# main_esp.net
KiCad netlist of a schematic drawn in Altium Designer
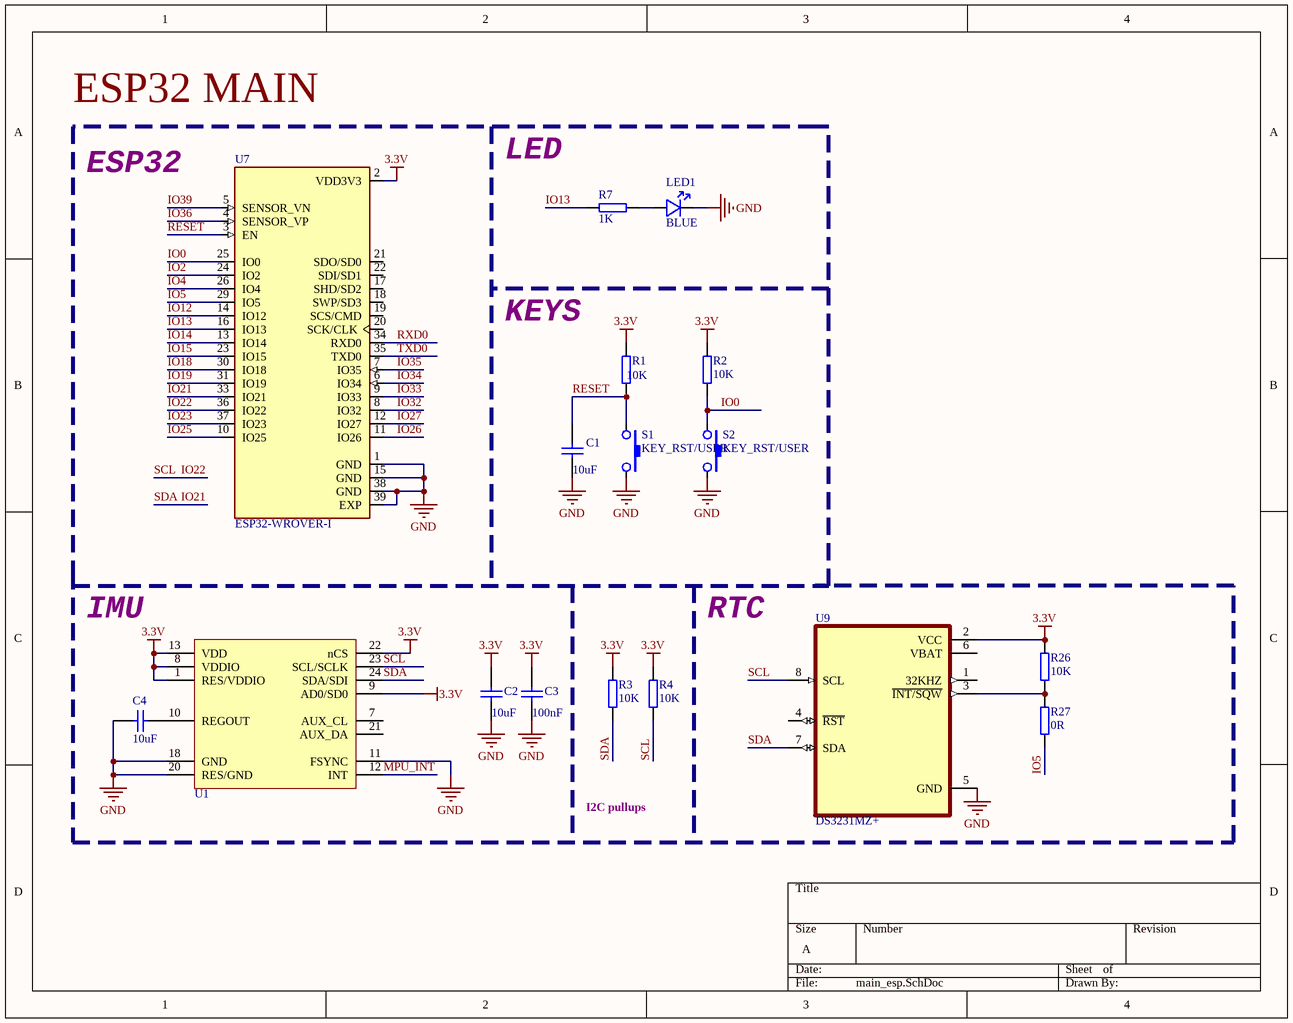
[diagram p0: main_esp.SchDoc]

(export (version "E")
  (design (tool "Eeschema 10.0.6"))
  (components
    (comp (ref "C1")
      (value "10uF")
      (footprint "SMT0603")
      (description "CAP SM 0603 X5R 10uF 10%")
      (fields (field (name "TOLERANCE") "±10%") (field (name "Comment") "Cap Semi"))
      (libsource (lib "electronpowered") (part "CAP-SM-0603-X5R-10uF"))
    )
    (comp (ref "C2")
      (value "10uF")
      (footprint "SMT0603")
      (description "CAP SM 0603 X5R 10uF 10%")
      (fields (field (name "TOLERANCE") "±10%") (field (name "Comment") "Cap Semi"))
      (libsource (lib "electronpowered") (part "CAP-SM-0603-X5R-10uF"))
    )
    (comp (ref "C3")
      (value "100nF")
      (footprint "SMT0603")
      (description "CAP SM 0603 X7R 100nF 10%")
      (fields (field (name "TOLERANCE") "±10%") (field (name "Comment") "Cap Semi"))
      (libsource (lib "electronpowered") (part "CAP-SM-0603-X7R-100nF"))
    )
    (comp (ref "C4")
      (value "10uF")
      (footprint "SMT0603")
      (description "CAP SM 0603 X5R 10uF 10%")
      (fields (field (name "TOLERANCE") "±10%") (field (name "Comment") "Cap Semi"))
      (libsource (lib "electronpowered") (part "CAP-SM-0603-X5R-10uF"))
    )
    (comp (ref "LED1")
      (value "BLUE")
      (footprint "SMT0603P")
      (description "LED SM 0603 BLUE 2V9 FWD VOLTAGE")
      (libsource (lib "electronpowered") (part "LNJ937W8CRA"))
    )
    (comp (ref "R1")
      (value "10K")
      (footprint "SMT0603")
      (description "RES SM 0603 10K")
      (fields (field (name "Comment") "Resistor"))
      (libsource (lib "electronpowered") (part "RES-SM-0603-10K"))
    )
    (comp (ref "R2")
      (value "10K")
      (footprint "SMT0603")
      (description "RES SM 0603 10K")
      (fields (field (name "Comment") "Resistor"))
      (libsource (lib "electronpowered") (part "RES-SM-0603-10K"))
    )
    (comp (ref "R3")
      (value "10K")
      (footprint "SMT0603")
      (description "RES SM 0603 10K")
      (fields (field (name "Comment") "Resistor"))
      (libsource (lib "electronpowered") (part "RES-SM-0603-10K"))
    )
    (comp (ref "R4")
      (value "10K")
      (footprint "SMT0603")
      (description "RES SM 0603 10K")
      (fields (field (name "Comment") "Resistor"))
      (libsource (lib "electronpowered") (part "RES-SM-0603-10K"))
    )
    (comp (ref "R7")
      (value "1K")
      (footprint "SMT0603")
      (description "RES SM 0603 1K")
      (fields (field (name "Comment") "Resistor"))
      (libsource (lib "electronpowered") (part "RES-SM-0603-1K"))
    )
    (comp (ref "R26")
      (value "10K")
      (footprint "SMT0603")
      (description "RES SM 0603 10K")
      (fields (field (name "Comment") "Resistor"))
      (libsource (lib "electronpowered") (part "RES-SM-0603-10K"))
    )
    (comp (ref "R27")
      (value "0R")
      (footprint "SMT0603")
      (description "RES SM 0603 10K")
      (fields (field (name "Comment") "Resistor"))
      (libsource (lib "electronpowered") (part "RES-SM-0603-10K"))
    )
    (comp (ref "S1")
      (value "KEY_RST/USER")
      (footprint "SMT_SW_PTS_820")
      (description "SMT Tactile ‎Switch PTS 820 Series")
      (libsource (lib "NODEMCU_DEVKIT_V1.0") (part "SMT_SW_PTS_820"))
    )
    (comp (ref "S2")
      (value "KEY_RST/USER")
      (footprint "SMT_SW_PTS_820")
      (description "SMT Tactile ‎Switch PTS 820 Series")
      (libsource (lib "NODEMCU_DEVKIT_V1.0") (part "SMT_SW_PTS_820"))
    )
    (comp (ref "U1") (value "MPU-9250") (libsource (lib "MPU-9250") (part "MPU-9250")))
    (comp (ref "U7")
      (value "ESP32-WROVER-I")
      (footprint "SnapEDApcb:XCVR_ESP32-WROVER-I")
      (fields (field (name "MF") "Espressif Systems"))
      (libsource (lib "SnapEDAsch") (part "ESP32-WROVER-I"))
    )
    (comp (ref "U9")
      (value "DS3231MZ+")
      (footprint "SOIC127P600X175-8N")
      (description "Real Time Clock _RTC_ IC Clock/Calendar IÂ²C, 2-Wire Serial 8-SOIC _0.154, 3.90mm Width_")
      (fields (field (name "MP") "DS3231MZ") (field (name "MF") "Maxim Integrated"))
      (libsource (lib "DS3231MZ_") (part "DS3231MZ+"))
    )
  )
  (nets
    (net (code "1") (name "/IO0") (class "Default")
      (node (ref "R2") (pin "1") (pinfunction "1_1") (pintype "passive"))
      (node (ref "S2") (pin "1") (pinfunction "1_1") (pintype "passive"))
      (node (ref "U7") (pin "25") (pinfunction "IO0_25") (pintype "bidirectional"))
    )
    (net (code "2") (name "/IO2") (class "Default")
      (node (ref "U7") (pin "24") (pinfunction "IO2_24") (pintype "bidirectional"))
    )
    (net (code "3") (name "/IO4") (class "Default")
      (node (ref "U7") (pin "26") (pinfunction "IO4_26") (pintype "bidirectional"))
    )
    (net (code "4") (name "/IO5") (class "Default")
      (node (ref "R27") (pin "2") (pinfunction "2_2") (pintype "passive"))
      (node (ref "U7") (pin "29") (pinfunction "IO5_29") (pintype "bidirectional"))
    )
    (net (code "5") (name "/IO12") (class "Default")
      (node (ref "U7") (pin "14") (pinfunction "IO12_14") (pintype "bidirectional"))
    )
    (net (code "6") (name "/IO13") (class "Default")
      (node (ref "R7") (pin "1") (pinfunction "1_1") (pintype "passive"))
      (node (ref "U7") (pin "16") (pinfunction "IO13_16") (pintype "bidirectional"))
    )
    (net (code "7") (name "/IO14") (class "Default")
      (node (ref "U7") (pin "13") (pinfunction "IO14_13") (pintype "bidirectional"))
    )
    (net (code "8") (name "/IO15") (class "Default")
      (node (ref "U7") (pin "23") (pinfunction "IO15_23") (pintype "bidirectional"))
    )
    (net (code "9") (name "/IO18") (class "Default")
      (node (ref "U7") (pin "30") (pinfunction "IO18_30") (pintype "bidirectional"))
    )
    (net (code "10") (name "/IO19") (class "Default")
      (node (ref "U7") (pin "31") (pinfunction "IO19_31") (pintype "bidirectional"))
    )
    (net (code "11") (name "/IO21") (class "Default")
      (node (ref "R3") (pin "1") (pinfunction "1_1") (pintype "passive"))
      (node (ref "U1") (pin "24") (pinfunction "SDA/SDI_24") (pintype "passive"))
      (node (ref "U7") (pin "33") (pinfunction "IO21_33") (pintype "bidirectional"))
      (node (ref "U9") (pin "7") (pinfunction "SDA_7") (pintype "bidirectional"))
    )
    (net (code "12") (name "/IO22") (class "Default")
      (node (ref "R4") (pin "1") (pinfunction "1_1") (pintype "passive"))
      (node (ref "U1") (pin "23") (pinfunction "SCL/SCLK_23") (pintype "passive"))
      (node (ref "U7") (pin "36") (pinfunction "IO22_36") (pintype "bidirectional"))
      (node (ref "U9") (pin "8") (pinfunction "SCL_8") (pintype "input"))
    )
    (net (code "13") (name "/IO23") (class "Default")
      (node (ref "U7") (pin "37") (pinfunction "IO23_37") (pintype "bidirectional"))
    )
    (net (code "14") (name "/IO25") (class "Default")
      (node (ref "U7") (pin "10") (pinfunction "IO25_10") (pintype "bidirectional"))
    )
    (net (code "15") (name "/IO26") (class "Default")
      (node (ref "U7") (pin "11") (pinfunction "IO26_11") (pintype "bidirectional"))
    )
    (net (code "16") (name "/IO27") (class "Default")
      (node (ref "U7") (pin "12") (pinfunction "IO27_12") (pintype "bidirectional"))
    )
    (net (code "17") (name "/IO32") (class "Default")
      (node (ref "U7") (pin "8") (pinfunction "IO32_8") (pintype "bidirectional"))
    )
    (net (code "18") (name "/IO33") (class "Default")
      (node (ref "U7") (pin "9") (pinfunction "IO33_9") (pintype "bidirectional"))
    )
    (net (code "19") (name "/IO34") (class "Default")
      (node (ref "U7") (pin "6") (pinfunction "IO34_6") (pintype "input"))
    )
    (net (code "20") (name "/IO35") (class "Default")
      (node (ref "U7") (pin "7") (pinfunction "IO35_7") (pintype "input"))
    )
    (net (code "21") (name "/IO36") (class "Default")
      (node (ref "U7") (pin "4") (pinfunction "SENSOR_VP_4") (pintype "input"))
    )
    (net (code "22") (name "/IO39") (class "Default")
      (node (ref "U7") (pin "5") (pinfunction "SENSOR_VN_5") (pintype "input"))
    )
    (net (code "23") (name "/MPU_INT") (class "Default")
      (node (ref "U1") (pin "12") (pinfunction "INT_12") (pintype "passive"))
    )
    (net (code "24") (name "/RESET") (class "Default")
      (node (ref "C1") (pin "2") (pinfunction "2_2") (pintype "passive"))
      (node (ref "R1") (pin "1") (pinfunction "1_1") (pintype "passive"))
      (node (ref "S1") (pin "1") (pinfunction "1_1") (pintype "passive"))
      (node (ref "U7") (pin "3") (pinfunction "EN_3") (pintype "input"))
    )
    (net (code "25") (name "/RXD0") (class "Default")
      (node (ref "U7") (pin "34") (pinfunction "RXD0_34") (pintype "bidirectional"))
    )
    (net (code "26") (name "/TXD0") (class "Default")
      (node (ref "U7") (pin "35") (pinfunction "TXD0_35") (pintype "bidirectional"))
    )
    (net (code "27") (name "3.3V") (class "Default")
      (node (ref "C2") (pin "2") (pinfunction "2_2") (pintype "passive"))
      (node (ref "C3") (pin "2") (pinfunction "2_2") (pintype "passive"))
      (node (ref "R1") (pin "2") (pinfunction "2_2") (pintype "passive"))
      (node (ref "R2") (pin "2") (pinfunction "2_2") (pintype "passive"))
      (node (ref "R26") (pin "1") (pinfunction "1_1") (pintype "passive"))
      (node (ref "R3") (pin "2") (pinfunction "2_2") (pintype "passive"))
      (node (ref "R4") (pin "2") (pinfunction "2_2") (pintype "passive"))
      (node (ref "U1") (pin "1") (pinfunction "RES/VDDIO_1") (pintype "passive"))
      (node (ref "U1") (pin "13") (pinfunction "VDD_13") (pintype "passive"))
      (node (ref "U1") (pin "22") (pinfunction "nCS_22") (pintype "passive"))
      (node (ref "U1") (pin "8") (pinfunction "VDDIO_8") (pintype "passive"))
      (node (ref "U1") (pin "9") (pinfunction "AD0/SD0_9") (pintype "passive"))
      (node (ref "U7") (pin "2") (pinfunction "VDD3V3_2") (pintype "power_in"))
      (node (ref "U9") (pin "2") (pinfunction "VCC_2") (pintype "power_in"))
    )
    (net (code "28") (name "GND") (class "Default")
      (node (ref "C1") (pin "1") (pinfunction "1_1") (pintype "passive"))
      (node (ref "C2") (pin "1") (pinfunction "1_1") (pintype "passive"))
      (node (ref "C3") (pin "1") (pinfunction "1_1") (pintype "passive"))
      (node (ref "C4") (pin "2") (pinfunction "2_2") (pintype "passive"))
      (node (ref "LED1") (pin "2") (pinfunction "2_2") (pintype "passive"))
      (node (ref "S1") (pin "2") (pinfunction "2_2") (pintype "passive"))
      (node (ref "S2") (pin "2") (pinfunction "2_2") (pintype "passive"))
      (node (ref "U1") (pin "11") (pinfunction "FSYNC_11") (pintype "passive"))
      (node (ref "U1") (pin "18") (pinfunction "GND_18") (pintype "passive"))
      (node (ref "U1") (pin "20") (pinfunction "RES/GND_20") (pintype "passive"))
      (node (ref "U7") (pin "1") (pinfunction "GND_1") (pintype "power_in"))
      (node (ref "U7") (pin "15") (pinfunction "GND_15") (pintype "power_in"))
      (node (ref "U7") (pin "38") (pinfunction "GND_38") (pintype "power_in"))
      (node (ref "U7") (pin "39") (pinfunction "EXP_39") (pintype "power_in"))
      (node (ref "U9") (pin "5") (pinfunction "GND_5") (pintype "power_in"))
    )
    (net (code "29") (name "Net-(LED1-Pad1)") (class "Default")
      (node (ref "LED1") (pin "1") (pinfunction "1_1") (pintype "passive"))
      (node (ref "R7") (pin "2") (pinfunction "2_2") (pintype "passive"))
    )
    (net (code "30") (name "Net-(U1-REGOUT)") (class "Default")
      (node (ref "C4") (pin "1") (pinfunction "1_1") (pintype "passive"))
      (node (ref "U1") (pin "10") (pinfunction "REGOUT_10") (pintype "passive"))
    )
    (net (code "31") (name "Net-(U9-~{INT{slash}SQW})") (class "Default")
      (node (ref "R26") (pin "2") (pinfunction "2_2") (pintype "passive"))
      (node (ref "R27") (pin "1") (pinfunction "1_1") (pintype "passive"))
      (node (ref "U9") (pin "3") (pinfunction "~{INT/SQW}_3") (pintype "output"))
    )
    (net (code "32") (name "unconnected-(U1-AUX_CL-Pad7)") (class "Default")
      (node (ref "U1") (pin "7") (pinfunction "AUX_CL_7") (pintype "passive"))
    )
    (net (code "33") (name "unconnected-(U1-AUX_DA-Pad21)") (class "Default")
      (node (ref "U1") (pin "21") (pinfunction "AUX_DA_21") (pintype "passive"))
    )
    (net (code "34") (name "unconnected-(U7-SCK{slash}CLK-Pad20)") (class "Default")
      (node (ref "U7") (pin "20") (pinfunction "SCK/CLK_20") (pintype "bidirectional"))
    )
    (net (code "35") (name "unconnected-(U7-SCS{slash}CMD-Pad19)") (class "Default")
      (node (ref "U7") (pin "19") (pinfunction "SCS/CMD_19") (pintype "bidirectional"))
    )
    (net (code "36") (name "unconnected-(U7-SDI{slash}SD1-Pad22)") (class "Default")
      (node (ref "U7") (pin "22") (pinfunction "SDI/SD1_22") (pintype "bidirectional"))
    )
    (net (code "37") (name "unconnected-(U7-SDO{slash}SD0-Pad21)") (class "Default")
      (node (ref "U7") (pin "21") (pinfunction "SDO/SD0_21") (pintype "bidirectional"))
    )
    (net (code "38") (name "unconnected-(U7-SHD{slash}SD2-Pad17)") (class "Default")
      (node (ref "U7") (pin "17") (pinfunction "SHD/SD2_17") (pintype "bidirectional"))
    )
    (net (code "39") (name "unconnected-(U7-SWP{slash}SD3-Pad18)") (class "Default")
      (node (ref "U7") (pin "18") (pinfunction "SWP/SD3_18") (pintype "bidirectional"))
    )
    (net (code "40") (name "unconnected-(U9-32KHZ-Pad1)") (class "Default")
      (node (ref "U9") (pin "1") (pinfunction "32KHZ_1") (pintype "output"))
    )
    (net (code "41") (name "unconnected-(U9-VBAT-Pad6)") (class "Default")
      (node (ref "U9") (pin "6") (pinfunction "VBAT_6") (pintype "power_in"))
    )
    (net (code "42") (name "unconnected-(U9-~{RST}-Pad4)") (class "Default")
      (node (ref "U9") (pin "4") (pinfunction "~{RST}_4") (pintype "bidirectional"))
    )
  )
)
